# BuckLedDriver.net
KiCad netlist of a schematic drawn in Altium Designer
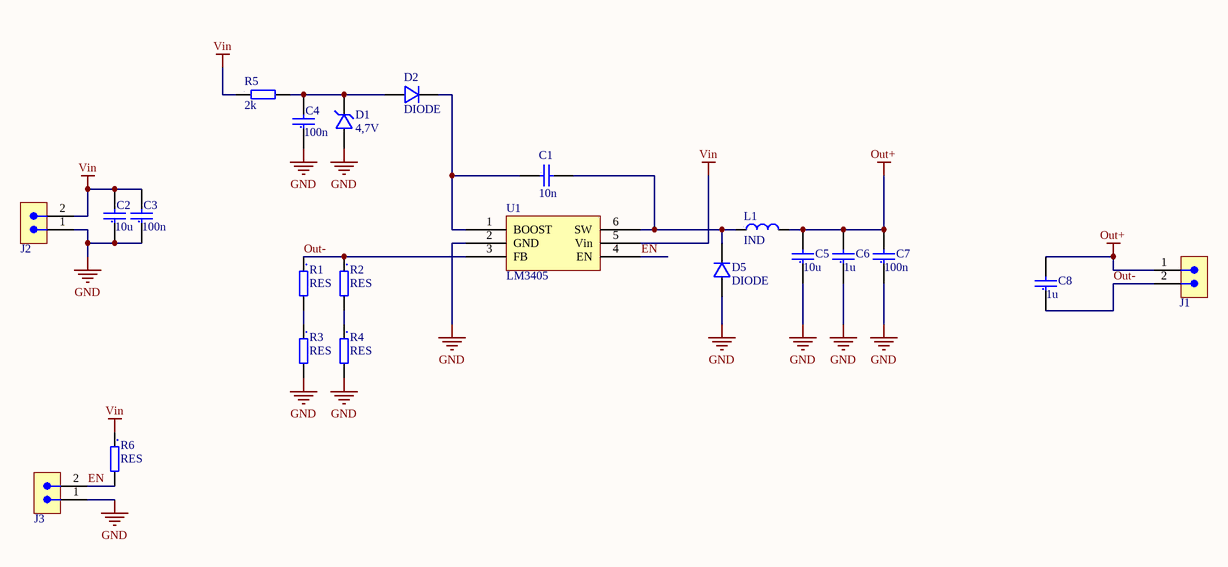
[diagram p0: BuckLedDriver.SchDoc]

(export (version "E")
  (design (tool "Eeschema 10.0.6"))
  (components
    (comp (ref "C1") (value "10n") (footprint "C0402_N") (libsource (lib "MyLib") (part "CAP")))
    (comp (ref "C2") (value "10u") (footprint "C0603_N") (libsource (lib "MyLib") (part "CAP")))
    (comp (ref "C3") (value "100n") (footprint "C0402_N") (libsource (lib "MyLib") (part "CAP")))
    (comp (ref "C4") (value "100n") (footprint "C0402_N") (libsource (lib "MyLib") (part "CAP")))
    (comp (ref "C5") (value "10u") (footprint "C0603_N") (libsource (lib "MyLib") (part "CAP")))
    (comp (ref "C6") (value "1u") (footprint "C0402_N") (libsource (lib "MyLib") (part "CAP")))
    (comp (ref "C7") (value "100n") (footprint "C0402_N") (libsource (lib "MyLib") (part "CAP")))
    (comp (ref "C8") (value "1u") (footprint "C0603_N") (libsource (lib "MyLib") (part "CAP")))
    (comp (ref "D1") (value "4,7V") (footprint "SOD-323") (libsource (lib "MyLib") (part "DIODE_ZENER")))
    (comp (ref "D2") (value "DIODE") (footprint "SOD-323") (libsource (lib "MyLib") (part "DIODE")))
    (comp (ref "D5") (value "DIODE") (footprint "SOD-323") (libsource (lib "MyLib") (part "DIODE")))
    (comp (ref "J1")
      (value "~")
      (footprint "B2B-XH-A")
      (description "Socket")
      (libsource (lib "") (part "PINHDR_2X1_1"))
    )
    (comp (ref "J2")
      (value "~")
      (footprint "B2B-XH-A")
      (description "Socket")
      (libsource (lib "MyLib") (part "PINHDR_2X1"))
    )
    (comp (ref "J3")
      (value "~")
      (footprint "B2B-XH-A")
      (description "Socket")
      (libsource (lib "MyLib") (part "PINHDR_2X1"))
    )
    (comp (ref "L1")
      (value "IND")
      (footprint "IHLP2020")
      (description "Inductor")
      (libsource (lib "MyLib") (part "IND"))
    )
    (comp (ref "R1") (value "RES") (footprint "R0805_N") (libsource (lib "MyLib") (part "RES")))
    (comp (ref "R2") (value "RES") (footprint "R0805_N") (libsource (lib "MyLib") (part "RES")))
    (comp (ref "R3") (value "RES") (footprint "R0805_N") (libsource (lib "MyLib") (part "RES")))
    (comp (ref "R4") (value "RES") (footprint "R0805_N") (libsource (lib "MyLib") (part "RES")))
    (comp (ref "R5") (value "2k") (footprint "R0603_N") (libsource (lib "MyLib") (part "RES")))
    (comp (ref "R6") (value "RES") (footprint "R0402_N") (libsource (lib "MyLib") (part "RES")))
    (comp (ref "U1")
      (value "LM3405")
      (footprint "SOT23-6")
      (description "1.6-MHz, 1-A Constant Current Buck LED Driver")
      (libsource (lib "MyLib") (part "LM3405"))
    )
  )
  (nets
    (net (code "1") (name "/EN") (class "Default")
      (node (ref "J3") (pin "2") (pinfunction "2_2") (pintype "passive"))
      (node (ref "R6") (pin "2") (pinfunction "2_2") (pintype "passive"))
      (node (ref "U1") (pin "4") (pinfunction "EN_4") (pintype "passive"))
    )
    (net (code "2") (name "/Out-") (class "Default")
      (node (ref "C8") (pin "1") (pinfunction "1_1") (pintype "passive"))
      (node (ref "J1") (pin "2") (pinfunction "2_2") (pintype "passive"))
      (node (ref "R1") (pin "1") (pinfunction "1_1") (pintype "passive"))
      (node (ref "R2") (pin "1") (pinfunction "1_1") (pintype "passive"))
      (node (ref "U1") (pin "3") (pinfunction "FB_3") (pintype "passive"))
    )
    (net (code "3") (name "GND") (class "Default")
      (node (ref "C2") (pin "1") (pinfunction "1_1") (pintype "passive"))
      (node (ref "C3") (pin "1") (pinfunction "1_1") (pintype "passive"))
      (node (ref "C4") (pin "1") (pinfunction "1_1") (pintype "passive"))
      (node (ref "C5") (pin "1") (pinfunction "1_1") (pintype "passive"))
      (node (ref "C6") (pin "1") (pinfunction "1_1") (pintype "passive"))
      (node (ref "C7") (pin "1") (pinfunction "1_1") (pintype "passive"))
      (node (ref "D1") (pin "A") (pinfunction "A_A") (pintype "passive"))
      (node (ref "D5") (pin "A") (pinfunction "A_A") (pintype "passive"))
      (node (ref "J2") (pin "1") (pinfunction "1_1") (pintype "passive"))
      (node (ref "J3") (pin "1") (pinfunction "1_1") (pintype "passive"))
      (node (ref "R3") (pin "2") (pinfunction "2_2") (pintype "passive"))
      (node (ref "R4") (pin "2") (pinfunction "2_2") (pintype "passive"))
      (node (ref "U1") (pin "2") (pinfunction "GND_2") (pintype "passive"))
    )
    (net (code "4") (name "Net-(C4-Pad2)") (class "Default")
      (node (ref "C4") (pin "2") (pinfunction "2_2") (pintype "passive"))
      (node (ref "D1") (pin "C") (pinfunction "C_C") (pintype "passive"))
      (node (ref "D2") (pin "A") (pinfunction "A_A") (pintype "passive"))
      (node (ref "R5") (pin "2") (pinfunction "2_2") (pintype "passive"))
    )
    (net (code "5") (name "Net-(R1-Pad2)") (class "Default")
      (node (ref "R1") (pin "2") (pinfunction "2_2") (pintype "passive"))
      (node (ref "R3") (pin "1") (pinfunction "1_1") (pintype "passive"))
    )
    (net (code "6") (name "Net-(R2-Pad2)") (class "Default")
      (node (ref "R2") (pin "2") (pinfunction "2_2") (pintype "passive"))
      (node (ref "R4") (pin "1") (pinfunction "1_1") (pintype "passive"))
    )
    (net (code "7") (name "Net-(U1-BOOST)") (class "Default")
      (node (ref "C1") (pin "1") (pinfunction "1_1") (pintype "passive"))
      (node (ref "D2") (pin "C") (pinfunction "C_C") (pintype "passive"))
      (node (ref "U1") (pin "1") (pinfunction "BOOST_1") (pintype "passive"))
    )
    (net (code "8") (name "Net-(U1-SW)") (class "Default")
      (node (ref "C1") (pin "2") (pinfunction "2_2") (pintype "passive"))
      (node (ref "D5") (pin "C") (pinfunction "C_C") (pintype "passive"))
      (node (ref "L1") (pin "1") (pinfunction "1_1") (pintype "passive"))
      (node (ref "U1") (pin "6") (pinfunction "SW_6") (pintype "passive"))
    )
    (net (code "9") (name "Out+") (class "Default")
      (node (ref "C5") (pin "2") (pinfunction "2_2") (pintype "passive"))
      (node (ref "C6") (pin "2") (pinfunction "2_2") (pintype "passive"))
      (node (ref "C7") (pin "2") (pinfunction "2_2") (pintype "passive"))
      (node (ref "C8") (pin "2") (pinfunction "2_2") (pintype "passive"))
      (node (ref "J1") (pin "1") (pinfunction "1_1") (pintype "passive"))
      (node (ref "L1") (pin "2") (pinfunction "2_2") (pintype "passive"))
    )
    (net (code "10") (name "Vin") (class "Default")
      (node (ref "C2") (pin "2") (pinfunction "2_2") (pintype "passive"))
      (node (ref "C3") (pin "2") (pinfunction "2_2") (pintype "passive"))
      (node (ref "J2") (pin "2") (pinfunction "2_2") (pintype "passive"))
      (node (ref "R5") (pin "1") (pinfunction "1_1") (pintype "passive"))
      (node (ref "R6") (pin "1") (pinfunction "1_1") (pintype "passive"))
      (node (ref "U1") (pin "5") (pinfunction "Vin_5") (pintype "passive"))
    )
  )
)
